# 6way.net
KiCad netlist of a schematic drawn in EAGLE
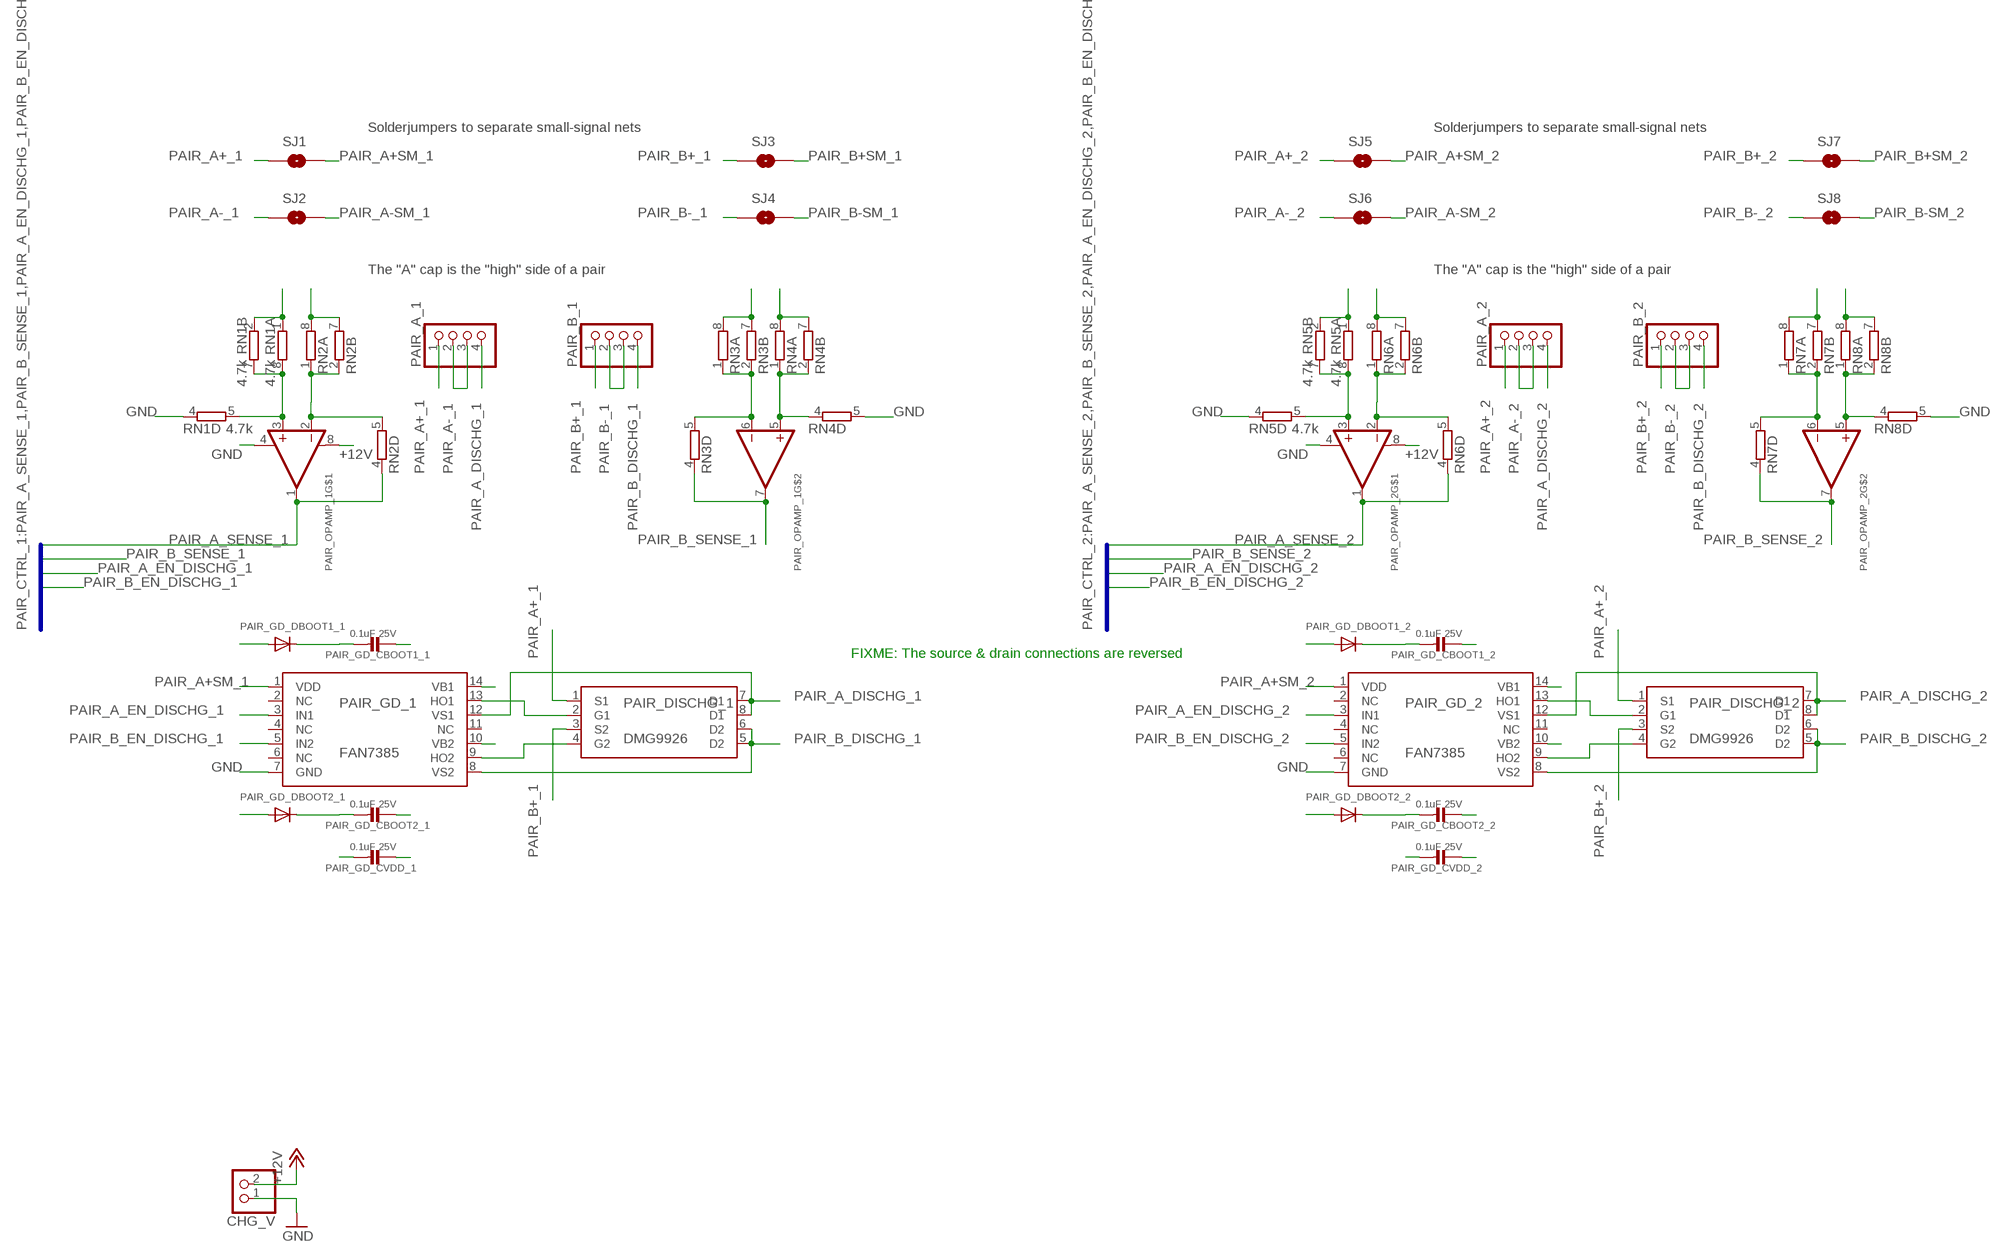
[diagram p0: schematic, sheet 1, part 1 of 2]
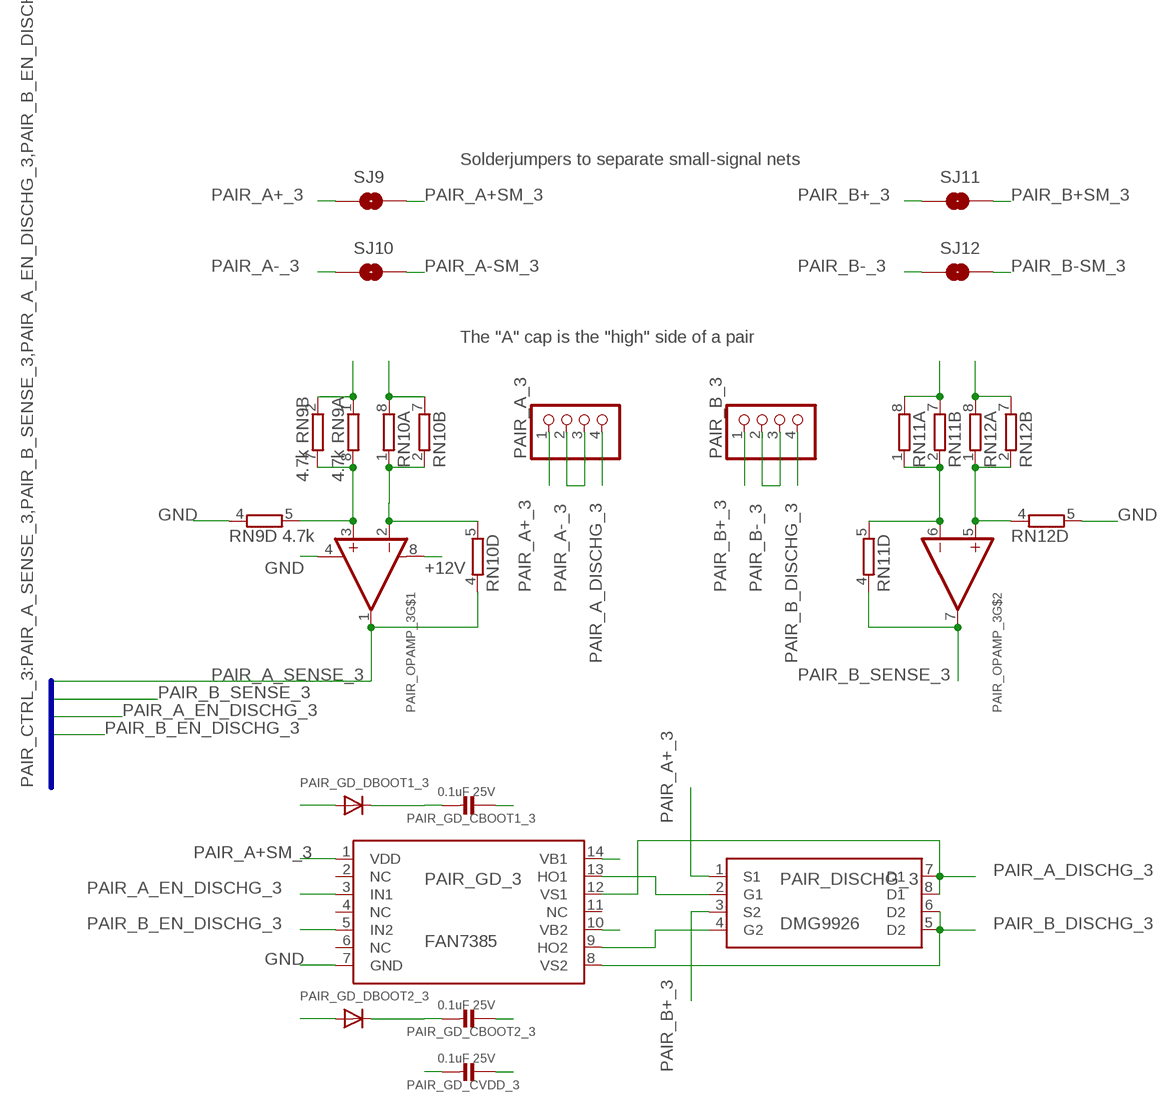
[diagram p1: schematic, sheet 1, part 2 of 2]

(export (version "E")
  (design (tool "Eeschema 10.0.6"))
  (components
    (comp (ref "CHG_V")
      (value "PINHD-1X2")
      (footprint "eagle-import:1X02")
      (libsource (lib "eagle-import") (part "PINHD-1X2"))
    )
    (comp (ref "PAIR_A_1")
      (value "PINHD-1X4")
      (footprint "eagle-import:1X04")
      (libsource (lib "eagle-import") (part "PINHD-1X4"))
    )
    (comp (ref "PAIR_A_2")
      (value "PINHD-1X4")
      (footprint "eagle-import:1X04")
      (libsource (lib "eagle-import") (part "PINHD-1X4"))
    )
    (comp (ref "PAIR_A_3")
      (value "PINHD-1X4")
      (footprint "eagle-import:1X04")
      (libsource (lib "eagle-import") (part "PINHD-1X4"))
    )
    (comp (ref "PAIR_B_1")
      (value "PINHD-1X4")
      (footprint "eagle-import:1X04")
      (libsource (lib "eagle-import") (part "PINHD-1X4"))
    )
    (comp (ref "PAIR_B_2")
      (value "PINHD-1X4")
      (footprint "eagle-import:1X04")
      (libsource (lib "eagle-import") (part "PINHD-1X4"))
    )
    (comp (ref "PAIR_B_3")
      (value "PINHD-1X4")
      (footprint "eagle-import:1X04")
      (libsource (lib "eagle-import") (part "PINHD-1X4"))
    )
    (comp (ref "PAIR_DISCHG_1")
      (value "DMG9926")
      (footprint "eagle-import:SOP8-L")
      (libsource (lib "eagle-import") (part "DMG9926"))
    )
    (comp (ref "PAIR_DISCHG_2")
      (value "DMG9926")
      (footprint "eagle-import:SOP8-L")
      (libsource (lib "eagle-import") (part "DMG9926"))
    )
    (comp (ref "PAIR_DISCHG_3")
      (value "DMG9926")
      (footprint "eagle-import:SOP8-L")
      (libsource (lib "eagle-import") (part "DMG9926"))
    )
    (comp (ref "PAIR_GD_1")
      (value "FAN7385")
      (footprint "eagle-import:SOT14")
      (libsource (lib "eagle-import") (part "FAN7385"))
    )
    (comp (ref "PAIR_GD_2")
      (value "FAN7385")
      (footprint "eagle-import:SOT14")
      (libsource (lib "eagle-import") (part "FAN7385"))
    )
    (comp (ref "PAIR_GD_3")
      (value "FAN7385")
      (footprint "eagle-import:SOT14")
      (libsource (lib "eagle-import") (part "FAN7385"))
    )
    (comp (ref "PAIR_GD_CBOOT1_1")
      (value "0.1uF 25V")
      (footprint "eagle-import:0805")
      (libsource (lib "eagle-import") (part "CAP_CERAMIC0805"))
    )
    (comp (ref "PAIR_GD_CBOOT1_2")
      (value "0.1uF 25V")
      (footprint "eagle-import:0805")
      (libsource (lib "eagle-import") (part "CAP_CERAMIC0805"))
    )
    (comp (ref "PAIR_GD_CBOOT1_3")
      (value "0.1uF 25V")
      (footprint "eagle-import:0805")
      (libsource (lib "eagle-import") (part "CAP_CERAMIC0805"))
    )
    (comp (ref "PAIR_GD_CBOOT2_1")
      (value "0.1uF 25V")
      (footprint "eagle-import:0805")
      (libsource (lib "eagle-import") (part "CAP_CERAMIC0805"))
    )
    (comp (ref "PAIR_GD_CBOOT2_2")
      (value "0.1uF 25V")
      (footprint "eagle-import:0805")
      (libsource (lib "eagle-import") (part "CAP_CERAMIC0805"))
    )
    (comp (ref "PAIR_GD_CBOOT2_3")
      (value "0.1uF 25V")
      (footprint "eagle-import:0805")
      (libsource (lib "eagle-import") (part "CAP_CERAMIC0805"))
    )
    (comp (ref "PAIR_GD_CVDD_1")
      (value "0.1uF 25V")
      (footprint "eagle-import:0805")
      (libsource (lib "eagle-import") (part "CAP_CERAMIC0805"))
    )
    (comp (ref "PAIR_GD_CVDD_2")
      (value "0.1uF 25V")
      (footprint "eagle-import:0805")
      (libsource (lib "eagle-import") (part "CAP_CERAMIC0805"))
    )
    (comp (ref "PAIR_GD_CVDD_3")
      (value "0.1uF 25V")
      (footprint "eagle-import:0805")
      (libsource (lib "eagle-import") (part "CAP_CERAMIC0805"))
    )
    (comp (ref "PAIR_GD_DBOOT1_1")
      (value "DIODESOT23_WIDE")
      (footprint "eagle-import:SOT23-WIDE")
      (libsource (lib "eagle-import") (part "DIODESOT23_WIDE"))
    )
    (comp (ref "PAIR_GD_DBOOT1_2")
      (value "DIODESOT23_WIDE")
      (footprint "eagle-import:SOT23-WIDE")
      (libsource (lib "eagle-import") (part "DIODESOT23_WIDE"))
    )
    (comp (ref "PAIR_GD_DBOOT1_3")
      (value "DIODESOT23_WIDE")
      (footprint "eagle-import:SOT23-WIDE")
      (libsource (lib "eagle-import") (part "DIODESOT23_WIDE"))
    )
    (comp (ref "PAIR_GD_DBOOT2_1")
      (value "DIODESOT23_WIDE")
      (footprint "eagle-import:SOT23-WIDE")
      (libsource (lib "eagle-import") (part "DIODESOT23_WIDE"))
    )
    (comp (ref "PAIR_GD_DBOOT2_2")
      (value "DIODESOT23_WIDE")
      (footprint "eagle-import:SOT23-WIDE")
      (libsource (lib "eagle-import") (part "DIODESOT23_WIDE"))
    )
    (comp (ref "PAIR_GD_DBOOT2_3")
      (value "DIODESOT23_WIDE")
      (footprint "eagle-import:SOT23-WIDE")
      (libsource (lib "eagle-import") (part "DIODESOT23_WIDE"))
    )
    (comp (ref "PAIR_OPAMP_1")
      (value "LM358")
      (footprint "eagle-import:SOIC8_150MIL")
      (libsource (lib "eagle-import") (part "LM358"))
    )
    (comp (ref "PAIR_OPAMP_2")
      (value "LM358")
      (footprint "eagle-import:SOIC8_150MIL")
      (libsource (lib "eagle-import") (part "LM358"))
    )
    (comp (ref "PAIR_OPAMP_3")
      (value "LM358")
      (footprint "eagle-import:SOIC8_150MIL")
      (libsource (lib "eagle-import") (part "LM358"))
    )
    (comp (ref "RN1")
      (value "4.7k")
      (footprint "eagle-import:CAY16")
      (libsource (lib "eagle-import") (part "4R-NCAY16"))
    )
    (comp (ref "RN2")
      (value "4R-NCAY16")
      (footprint "eagle-import:CAY16")
      (libsource (lib "eagle-import") (part "4R-NCAY16"))
    )
    (comp (ref "RN3")
      (value "4R-NCAY16")
      (footprint "eagle-import:CAY16")
      (libsource (lib "eagle-import") (part "4R-NCAY16"))
    )
    (comp (ref "RN4")
      (value "4R-NCAY16")
      (footprint "eagle-import:CAY16")
      (libsource (lib "eagle-import") (part "4R-NCAY16"))
    )
    (comp (ref "RN5")
      (value "4.7k")
      (footprint "eagle-import:CAY16")
      (libsource (lib "eagle-import") (part "4R-NCAY16"))
    )
    (comp (ref "RN6")
      (value "4R-NCAY16")
      (footprint "eagle-import:CAY16")
      (libsource (lib "eagle-import") (part "4R-NCAY16"))
    )
    (comp (ref "RN7")
      (value "4R-NCAY16")
      (footprint "eagle-import:CAY16")
      (libsource (lib "eagle-import") (part "4R-NCAY16"))
    )
    (comp (ref "RN8")
      (value "4R-NCAY16")
      (footprint "eagle-import:CAY16")
      (libsource (lib "eagle-import") (part "4R-NCAY16"))
    )
    (comp (ref "RN9")
      (value "4.7k")
      (footprint "eagle-import:CAY16")
      (libsource (lib "eagle-import") (part "4R-NCAY16"))
    )
    (comp (ref "RN10")
      (value "4R-NCAY16")
      (footprint "eagle-import:CAY16")
      (libsource (lib "eagle-import") (part "4R-NCAY16"))
    )
    (comp (ref "RN11")
      (value "4R-NCAY16")
      (footprint "eagle-import:CAY16")
      (libsource (lib "eagle-import") (part "4R-NCAY16"))
    )
    (comp (ref "RN12")
      (value "4R-NCAY16")
      (footprint "eagle-import:CAY16")
      (libsource (lib "eagle-import") (part "4R-NCAY16"))
    )
    (comp (ref "SJ1")
      (value "SOLDERJUMPERTRACE")
      (footprint "eagle-import:SJ_2S-TRACE")
      (libsource (lib "eagle-import") (part "SOLDERJUMPERTRACE"))
    )
    (comp (ref "SJ2")
      (value "SOLDERJUMPERTRACE")
      (footprint "eagle-import:SJ_2S-TRACE")
      (libsource (lib "eagle-import") (part "SOLDERJUMPERTRACE"))
    )
    (comp (ref "SJ3")
      (value "SOLDERJUMPERTRACE")
      (footprint "eagle-import:SJ_2S-TRACE")
      (libsource (lib "eagle-import") (part "SOLDERJUMPERTRACE"))
    )
    (comp (ref "SJ4")
      (value "SOLDERJUMPERTRACE")
      (footprint "eagle-import:SJ_2S-TRACE")
      (libsource (lib "eagle-import") (part "SOLDERJUMPERTRACE"))
    )
    (comp (ref "SJ5")
      (value "SOLDERJUMPERTRACE")
      (footprint "eagle-import:SJ_2S-TRACE")
      (libsource (lib "eagle-import") (part "SOLDERJUMPERTRACE"))
    )
    (comp (ref "SJ6")
      (value "SOLDERJUMPERTRACE")
      (footprint "eagle-import:SJ_2S-TRACE")
      (libsource (lib "eagle-import") (part "SOLDERJUMPERTRACE"))
    )
    (comp (ref "SJ7")
      (value "SOLDERJUMPERTRACE")
      (footprint "eagle-import:SJ_2S-TRACE")
      (libsource (lib "eagle-import") (part "SOLDERJUMPERTRACE"))
    )
    (comp (ref "SJ8")
      (value "SOLDERJUMPERTRACE")
      (footprint "eagle-import:SJ_2S-TRACE")
      (libsource (lib "eagle-import") (part "SOLDERJUMPERTRACE"))
    )
    (comp (ref "SJ9")
      (value "SOLDERJUMPERTRACE")
      (footprint "eagle-import:SJ_2S-TRACE")
      (libsource (lib "eagle-import") (part "SOLDERJUMPERTRACE"))
    )
    (comp (ref "SJ10")
      (value "SOLDERJUMPERTRACE")
      (footprint "eagle-import:SJ_2S-TRACE")
      (libsource (lib "eagle-import") (part "SOLDERJUMPERTRACE"))
    )
    (comp (ref "SJ11")
      (value "SOLDERJUMPERTRACE")
      (footprint "eagle-import:SJ_2S-TRACE")
      (libsource (lib "eagle-import") (part "SOLDERJUMPERTRACE"))
    )
    (comp (ref "SJ12")
      (value "SOLDERJUMPERTRACE")
      (footprint "eagle-import:SJ_2S-TRACE")
      (libsource (lib "eagle-import") (part "SOLDERJUMPERTRACE"))
    )
  )
  (nets
    (net (code "4") (name "+12V") (class "Default")
      (node (ref "CHG_V") (pin "2") (pinfunction "2_2") (pintype "passive"))
      (node (ref "PAIR_OPAMP_1") (pin "8") (pinfunction "V+_8") (pintype "power_in"))
      (node (ref "PAIR_OPAMP_2") (pin "8") (pinfunction "V+_8") (pintype "power_in"))
      (node (ref "PAIR_OPAMP_3") (pin "8") (pinfunction "V+_8") (pintype "power_in"))
    )
    (net (code "5") (name "/PAIR_A+SM_1") (class "Default")
      (node (ref "PAIR_GD_1") (pin "1") (pinfunction "VDD_1") (pintype "power_in"))
      (node (ref "PAIR_GD_CVDD_1") (pin "2") (pinfunction "P$2_2") (pintype "passive"))
      (node (ref "PAIR_GD_DBOOT1_1") (pin "1") (pinfunction "A_1") (pintype "passive"))
      (node (ref "PAIR_GD_DBOOT2_1") (pin "1") (pinfunction "A_1") (pintype "passive"))
      (node (ref "RN1") (pin "1") (pinfunction "1_1") (pintype "passive"))
      (node (ref "RN1") (pin "2") (pinfunction "1_2") (pintype "passive"))
      (node (ref "SJ1") (pin "2") (pinfunction "2_2") (pintype "passive"))
    )
    (net (code "6") (name "/PAIR_A+SM_2") (class "Default")
      (node (ref "PAIR_GD_2") (pin "1") (pinfunction "VDD_1") (pintype "power_in"))
      (node (ref "PAIR_GD_CVDD_2") (pin "2") (pinfunction "P$2_2") (pintype "passive"))
      (node (ref "PAIR_GD_DBOOT1_2") (pin "1") (pinfunction "A_1") (pintype "passive"))
      (node (ref "PAIR_GD_DBOOT2_2") (pin "1") (pinfunction "A_1") (pintype "passive"))
      (node (ref "RN5") (pin "1") (pinfunction "1_1") (pintype "passive"))
      (node (ref "RN5") (pin "2") (pinfunction "1_2") (pintype "passive"))
      (node (ref "SJ5") (pin "2") (pinfunction "2_2") (pintype "passive"))
    )
    (net (code "7") (name "/PAIR_A+SM_3") (class "Default")
      (node (ref "PAIR_GD_3") (pin "1") (pinfunction "VDD_1") (pintype "power_in"))
      (node (ref "PAIR_GD_CVDD_3") (pin "2") (pinfunction "P$2_2") (pintype "passive"))
      (node (ref "PAIR_GD_DBOOT1_3") (pin "1") (pinfunction "A_1") (pintype "passive"))
      (node (ref "PAIR_GD_DBOOT2_3") (pin "1") (pinfunction "A_1") (pintype "passive"))
      (node (ref "RN9") (pin "1") (pinfunction "1_1") (pintype "passive"))
      (node (ref "RN9") (pin "2") (pinfunction "1_2") (pintype "passive"))
      (node (ref "SJ9") (pin "2") (pinfunction "2_2") (pintype "passive"))
    )
    (net (code "8") (name "/PAIR_A+_1") (class "Default")
      (node (ref "PAIR_A_1") (pin "1") (pinfunction "1_1") (pintype "passive"))
      (node (ref "PAIR_DISCHG_1") (pin "1") (pinfunction "S1_1") (pintype "input"))
      (node (ref "SJ1") (pin "1") (pinfunction "1_1") (pintype "passive"))
    )
    (net (code "9") (name "/PAIR_A+_2") (class "Default")
      (node (ref "PAIR_A_2") (pin "1") (pinfunction "1_1") (pintype "passive"))
      (node (ref "PAIR_DISCHG_2") (pin "1") (pinfunction "S1_1") (pintype "input"))
      (node (ref "SJ5") (pin "1") (pinfunction "1_1") (pintype "passive"))
    )
    (net (code "10") (name "/PAIR_A+_3") (class "Default")
      (node (ref "PAIR_A_3") (pin "1") (pinfunction "1_1") (pintype "passive"))
      (node (ref "PAIR_DISCHG_3") (pin "1") (pinfunction "S1_1") (pintype "input"))
      (node (ref "SJ9") (pin "1") (pinfunction "1_1") (pintype "passive"))
    )
    (net (code "11") (name "/PAIR_A-SM_1") (class "Default")
      (node (ref "RN2") (pin "7") (pinfunction "2_7") (pintype "passive"))
      (node (ref "RN2") (pin "8") (pinfunction "2_8") (pintype "passive"))
      (node (ref "SJ2") (pin "2") (pinfunction "2_2") (pintype "passive"))
    )
    (net (code "12") (name "/PAIR_A-SM_2") (class "Default")
      (node (ref "RN6") (pin "7") (pinfunction "2_7") (pintype "passive"))
      (node (ref "RN6") (pin "8") (pinfunction "2_8") (pintype "passive"))
      (node (ref "SJ6") (pin "2") (pinfunction "2_2") (pintype "passive"))
    )
    (net (code "13") (name "/PAIR_A-SM_3") (class "Default")
      (node (ref "RN10") (pin "7") (pinfunction "2_7") (pintype "passive"))
      (node (ref "RN10") (pin "8") (pinfunction "2_8") (pintype "passive"))
      (node (ref "SJ10") (pin "2") (pinfunction "2_2") (pintype "passive"))
    )
    (net (code "14") (name "/PAIR_A-_1") (class "Default")
      (node (ref "PAIR_A_1") (pin "2") (pinfunction "2_2") (pintype "passive"))
      (node (ref "PAIR_A_1") (pin "3") (pinfunction "3_3") (pintype "passive"))
      (node (ref "SJ2") (pin "1") (pinfunction "1_1") (pintype "passive"))
    )
    (net (code "15") (name "/PAIR_A-_2") (class "Default")
      (node (ref "PAIR_A_2") (pin "2") (pinfunction "2_2") (pintype "passive"))
      (node (ref "PAIR_A_2") (pin "3") (pinfunction "3_3") (pintype "passive"))
      (node (ref "SJ6") (pin "1") (pinfunction "1_1") (pintype "passive"))
    )
    (net (code "16") (name "/PAIR_A-_3") (class "Default")
      (node (ref "PAIR_A_3") (pin "2") (pinfunction "2_2") (pintype "passive"))
      (node (ref "PAIR_A_3") (pin "3") (pinfunction "3_3") (pintype "passive"))
      (node (ref "SJ10") (pin "1") (pinfunction "1_1") (pintype "passive"))
    )
    (net (code "17") (name "/PAIR_A_DISCHG_1") (class "Default")
      (node (ref "PAIR_A_1") (pin "4") (pinfunction "4_4") (pintype "passive"))
      (node (ref "PAIR_DISCHG_1") (pin "7") (pinfunction "D1_7") (pintype "output"))
      (node (ref "PAIR_DISCHG_1") (pin "8") (pinfunction "D1_8") (pintype "output"))
      (node (ref "PAIR_GD_1") (pin "12") (pinfunction "VS1_12") (pintype "input"))
      (node (ref "PAIR_GD_CBOOT1_1") (pin "1") (pinfunction "P$1_1") (pintype "passive"))
    )
    (net (code "18") (name "/PAIR_A_DISCHG_2") (class "Default")
      (node (ref "PAIR_A_2") (pin "4") (pinfunction "4_4") (pintype "passive"))
      (node (ref "PAIR_DISCHG_2") (pin "7") (pinfunction "D1_7") (pintype "output"))
      (node (ref "PAIR_DISCHG_2") (pin "8") (pinfunction "D1_8") (pintype "output"))
      (node (ref "PAIR_GD_2") (pin "12") (pinfunction "VS1_12") (pintype "input"))
      (node (ref "PAIR_GD_CBOOT1_2") (pin "1") (pinfunction "P$1_1") (pintype "passive"))
    )
    (net (code "19") (name "/PAIR_A_DISCHG_3") (class "Default")
      (node (ref "PAIR_A_3") (pin "4") (pinfunction "4_4") (pintype "passive"))
      (node (ref "PAIR_DISCHG_3") (pin "7") (pinfunction "D1_7") (pintype "output"))
      (node (ref "PAIR_DISCHG_3") (pin "8") (pinfunction "D1_8") (pintype "output"))
      (node (ref "PAIR_GD_3") (pin "12") (pinfunction "VS1_12") (pintype "input"))
      (node (ref "PAIR_GD_CBOOT1_3") (pin "1") (pinfunction "P$1_1") (pintype "passive"))
    )
    (net (code "20") (name "/PAIR_A_EN_DISCHG_1") (class "Default")
      (node (ref "PAIR_GD_1") (pin "3") (pinfunction "IN1_3") (pintype "input"))
    )
    (net (code "21") (name "/PAIR_A_EN_DISCHG_2") (class "Default")
      (node (ref "PAIR_GD_2") (pin "3") (pinfunction "IN1_3") (pintype "input"))
    )
    (net (code "22") (name "/PAIR_A_EN_DISCHG_3") (class "Default")
      (node (ref "PAIR_GD_3") (pin "3") (pinfunction "IN1_3") (pintype "input"))
    )
    (net (code "23") (name "/PAIR_A_SENSE_1") (class "Default")
      (node (ref "PAIR_OPAMP_1") (pin "1") (pinfunction "OUT_1") (pintype "output"))
      (node (ref "RN2") (pin "4") (pinfunction "1_4") (pintype "passive"))
    )
    (net (code "24") (name "/PAIR_A_SENSE_2") (class "Default")
      (node (ref "PAIR_OPAMP_2") (pin "1") (pinfunction "OUT_1") (pintype "output"))
      (node (ref "RN6") (pin "4") (pinfunction "1_4") (pintype "passive"))
    )
    (net (code "25") (name "/PAIR_A_SENSE_3") (class "Default")
      (node (ref "PAIR_OPAMP_3") (pin "1") (pinfunction "OUT_1") (pintype "output"))
      (node (ref "RN10") (pin "4") (pinfunction "1_4") (pintype "passive"))
    )
    (net (code "26") (name "/PAIR_B+SM_1") (class "Default")
      (node (ref "RN4") (pin "7") (pinfunction "2_7") (pintype "passive"))
      (node (ref "RN4") (pin "8") (pinfunction "2_8") (pintype "passive"))
      (node (ref "SJ3") (pin "2") (pinfunction "2_2") (pintype "passive"))
    )
    (net (code "27") (name "/PAIR_B+SM_2") (class "Default")
      (node (ref "RN8") (pin "7") (pinfunction "2_7") (pintype "passive"))
      (node (ref "RN8") (pin "8") (pinfunction "2_8") (pintype "passive"))
      (node (ref "SJ7") (pin "2") (pinfunction "2_2") (pintype "passive"))
    )
    (net (code "28") (name "/PAIR_B+SM_3") (class "Default")
      (node (ref "RN12") (pin "7") (pinfunction "2_7") (pintype "passive"))
      (node (ref "RN12") (pin "8") (pinfunction "2_8") (pintype "passive"))
      (node (ref "SJ11") (pin "2") (pinfunction "2_2") (pintype "passive"))
    )
    (net (code "29") (name "/PAIR_B+_1") (class "Default")
      (node (ref "PAIR_B_1") (pin "1") (pinfunction "1_1") (pintype "passive"))
      (node (ref "PAIR_DISCHG_1") (pin "3") (pinfunction "S2_3") (pintype "input"))
      (node (ref "SJ3") (pin "1") (pinfunction "1_1") (pintype "passive"))
    )
    (net (code "30") (name "/PAIR_B+_2") (class "Default")
      (node (ref "PAIR_B_2") (pin "1") (pinfunction "1_1") (pintype "passive"))
      (node (ref "PAIR_DISCHG_2") (pin "3") (pinfunction "S2_3") (pintype "input"))
      (node (ref "SJ7") (pin "1") (pinfunction "1_1") (pintype "passive"))
    )
    (net (code "31") (name "/PAIR_B+_3") (class "Default")
      (node (ref "PAIR_B_3") (pin "1") (pinfunction "1_1") (pintype "passive"))
      (node (ref "PAIR_DISCHG_3") (pin "3") (pinfunction "S2_3") (pintype "input"))
      (node (ref "SJ11") (pin "1") (pinfunction "1_1") (pintype "passive"))
    )
    (net (code "32") (name "/PAIR_B-SM_1") (class "Default")
      (node (ref "RN3") (pin "7") (pinfunction "2_7") (pintype "passive"))
      (node (ref "RN3") (pin "8") (pinfunction "2_8") (pintype "passive"))
      (node (ref "SJ4") (pin "2") (pinfunction "2_2") (pintype "passive"))
    )
    (net (code "33") (name "/PAIR_B-SM_2") (class "Default")
      (node (ref "RN7") (pin "7") (pinfunction "2_7") (pintype "passive"))
      (node (ref "RN7") (pin "8") (pinfunction "2_8") (pintype "passive"))
      (node (ref "SJ8") (pin "2") (pinfunction "2_2") (pintype "passive"))
    )
    (net (code "34") (name "/PAIR_B-SM_3") (class "Default")
      (node (ref "RN11") (pin "7") (pinfunction "2_7") (pintype "passive"))
      (node (ref "RN11") (pin "8") (pinfunction "2_8") (pintype "passive"))
      (node (ref "SJ12") (pin "2") (pinfunction "2_2") (pintype "passive"))
    )
    (net (code "35") (name "/PAIR_B-_1") (class "Default")
      (node (ref "PAIR_B_1") (pin "2") (pinfunction "2_2") (pintype "passive"))
      (node (ref "PAIR_B_1") (pin "3") (pinfunction "3_3") (pintype "passive"))
      (node (ref "SJ4") (pin "1") (pinfunction "1_1") (pintype "passive"))
    )
    (net (code "36") (name "/PAIR_B-_2") (class "Default")
      (node (ref "PAIR_B_2") (pin "2") (pinfunction "2_2") (pintype "passive"))
      (node (ref "PAIR_B_2") (pin "3") (pinfunction "3_3") (pintype "passive"))
      (node (ref "SJ8") (pin "1") (pinfunction "1_1") (pintype "passive"))
    )
    (net (code "37") (name "/PAIR_B-_3") (class "Default")
      (node (ref "PAIR_B_3") (pin "2") (pinfunction "2_2") (pintype "passive"))
      (node (ref "PAIR_B_3") (pin "3") (pinfunction "3_3") (pintype "passive"))
      (node (ref "SJ12") (pin "1") (pinfunction "1_1") (pintype "passive"))
    )
    (net (code "38") (name "/PAIR_B_DISCHG_1") (class "Default")
      (node (ref "PAIR_B_1") (pin "4") (pinfunction "4_4") (pintype "passive"))
      (node (ref "PAIR_DISCHG_1") (pin "5") (pinfunction "D2_5") (pintype "output"))
      (node (ref "PAIR_DISCHG_1") (pin "6") (pinfunction "D2_6") (pintype "output"))
      (node (ref "PAIR_GD_1") (pin "8") (pinfunction "VS2_8") (pintype "input"))
      (node (ref "PAIR_GD_CBOOT2_1") (pin "1") (pinfunction "P$1_1") (pintype "passive"))
    )
    (net (code "39") (name "/PAIR_B_DISCHG_2") (class "Default")
      (node (ref "PAIR_B_2") (pin "4") (pinfunction "4_4") (pintype "passive"))
      (node (ref "PAIR_DISCHG_2") (pin "5") (pinfunction "D2_5") (pintype "output"))
      (node (ref "PAIR_DISCHG_2") (pin "6") (pinfunction "D2_6") (pintype "output"))
      (node (ref "PAIR_GD_2") (pin "8") (pinfunction "VS2_8") (pintype "input"))
      (node (ref "PAIR_GD_CBOOT2_2") (pin "1") (pinfunction "P$1_1") (pintype "passive"))
    )
    (net (code "40") (name "/PAIR_B_DISCHG_3") (class "Default")
      (node (ref "PAIR_B_3") (pin "4") (pinfunction "4_4") (pintype "passive"))
      (node (ref "PAIR_DISCHG_3") (pin "5") (pinfunction "D2_5") (pintype "output"))
      (node (ref "PAIR_DISCHG_3") (pin "6") (pinfunction "D2_6") (pintype "output"))
      (node (ref "PAIR_GD_3") (pin "8") (pinfunction "VS2_8") (pintype "input"))
      (node (ref "PAIR_GD_CBOOT2_3") (pin "1") (pinfunction "P$1_1") (pintype "passive"))
    )
    (net (code "41") (name "/PAIR_B_EN_DISCHG_1") (class "Default")
      (node (ref "PAIR_GD_1") (pin "5") (pinfunction "IN2_5") (pintype "input"))
    )
    (net (code "42") (name "/PAIR_B_EN_DISCHG_2") (class "Default")
      (node (ref "PAIR_GD_2") (pin "5") (pinfunction "IN2_5") (pintype "input"))
    )
    (net (code "43") (name "/PAIR_B_EN_DISCHG_3") (class "Default")
      (node (ref "PAIR_GD_3") (pin "5") (pinfunction "IN2_5") (pintype "input"))
    )
    (net (code "44") (name "/PAIR_B_SENSE_1") (class "Default")
      (node (ref "PAIR_OPAMP_1") (pin "7") (pinfunction "OUT_7") (pintype "output"))
      (node (ref "RN3") (pin "4") (pinfunction "1_4") (pintype "passive"))
    )
    (net (code "45") (name "/PAIR_B_SENSE_2") (class "Default")
      (node (ref "PAIR_OPAMP_2") (pin "7") (pinfunction "OUT_7") (pintype "output"))
      (node (ref "RN7") (pin "4") (pinfunction "1_4") (pintype "passive"))
    )
    (net (code "46") (name "/PAIR_B_SENSE_3") (class "Default")
      (node (ref "PAIR_OPAMP_3") (pin "7") (pinfunction "OUT_7") (pintype "output"))
      (node (ref "RN11") (pin "4") (pinfunction "1_4") (pintype "passive"))
    )
    (net (code "47") (name "/PAIR_GD_VB1_1") (class "Default")
      (node (ref "PAIR_GD_1") (pin "14") (pinfunction "VB1_14") (pintype "input"))
      (node (ref "PAIR_GD_CBOOT1_1") (pin "2") (pinfunction "P$2_2") (pintype "passive"))
      (node (ref "PAIR_GD_DBOOT1_1") (pin "3") (pinfunction "C_3") (pintype "passive"))
    )
    (net (code "48") (name "/PAIR_GD_VB1_2") (class "Default")
      (node (ref "PAIR_GD_2") (pin "14") (pinfunction "VB1_14") (pintype "input"))
      (node (ref "PAIR_GD_CBOOT1_2") (pin "2") (pinfunction "P$2_2") (pintype "passive"))
      (node (ref "PAIR_GD_DBOOT1_2") (pin "3") (pinfunction "C_3") (pintype "passive"))
    )
    (net (code "49") (name "/PAIR_GD_VB1_3") (class "Default")
      (node (ref "PAIR_GD_3") (pin "14") (pinfunction "VB1_14") (pintype "input"))
      (node (ref "PAIR_GD_CBOOT1_3") (pin "2") (pinfunction "P$2_2") (pintype "passive"))
      (node (ref "PAIR_GD_DBOOT1_3") (pin "3") (pinfunction "C_3") (pintype "passive"))
    )
    (net (code "50") (name "/PAIR_GD_VB2_1") (class "Default")
      (node (ref "PAIR_GD_1") (pin "10") (pinfunction "VB2_10") (pintype "input"))
      (node (ref "PAIR_GD_CBOOT2_1") (pin "2") (pinfunction "P$2_2") (pintype "passive"))
      (node (ref "PAIR_GD_DBOOT2_1") (pin "3") (pinfunction "C_3") (pintype "passive"))
    )
    (net (code "51") (name "/PAIR_GD_VB2_2") (class "Default")
      (node (ref "PAIR_GD_2") (pin "10") (pinfunction "VB2_10") (pintype "input"))
      (node (ref "PAIR_GD_CBOOT2_2") (pin "2") (pinfunction "P$2_2") (pintype "passive"))
      (node (ref "PAIR_GD_DBOOT2_2") (pin "3") (pinfunction "C_3") (pintype "passive"))
    )
    (net (code "52") (name "/PAIR_GD_VB2_3") (class "Default")
      (node (ref "PAIR_GD_3") (pin "10") (pinfunction "VB2_10") (pintype "input"))
      (node (ref "PAIR_GD_CBOOT2_3") (pin "2") (pinfunction "P$2_2") (pintype "passive"))
      (node (ref "PAIR_GD_DBOOT2_3") (pin "3") (pinfunction "C_3") (pintype "passive"))
    )
    (net (code "56") (name "GND") (class "Default")
      (node (ref "CHG_V") (pin "1") (pinfunction "1_1") (pintype "passive"))
      (node (ref "PAIR_GD_1") (pin "7") (pinfunction "GND_7") (pintype "power_in"))
      (node (ref "PAIR_GD_2") (pin "7") (pinfunction "GND_7") (pintype "power_in"))
      (node (ref "PAIR_GD_3") (pin "7") (pinfunction "GND_7") (pintype "power_in"))
      (node (ref "PAIR_GD_CVDD_1") (pin "1") (pinfunction "P$1_1") (pintype "passive"))
      (node (ref "PAIR_GD_CVDD_2") (pin "1") (pinfunction "P$1_1") (pintype "passive"))
      (node (ref "PAIR_GD_CVDD_3") (pin "1") (pinfunction "P$1_1") (pintype "passive"))
      (node (ref "PAIR_OPAMP_1") (pin "4") (pinfunction "V-_4") (pintype "power_in"))
      (node (ref "PAIR_OPAMP_2") (pin "4") (pinfunction "V-_4") (pintype "power_in"))
      (node (ref "PAIR_OPAMP_3") (pin "4") (pinfunction "V-_4") (pintype "power_in"))
      (node (ref "RN1") (pin "4") (pinfunction "1_4") (pintype "passive"))
      (node (ref "RN12") (pin "5") (pinfunction "2_5") (pintype "passive"))
      (node (ref "RN4") (pin "5") (pinfunction "2_5") (pintype "passive"))
      (node (ref "RN5") (pin "4") (pinfunction "1_4") (pintype "passive"))
      (node (ref "RN8") (pin "5") (pinfunction "2_5") (pintype "passive"))
      (node (ref "RN9") (pin "4") (pinfunction "1_4") (pintype "passive"))
    )
    (net (code "57") (name "Net-(PAIR_DISCHG_1-G1)") (class "Default")
      (node (ref "PAIR_DISCHG_1") (pin "2") (pinfunction "G1_2") (pintype "input"))
      (node (ref "PAIR_GD_1") (pin "13") (pinfunction "HO1_13") (pintype "output"))
    )
    (net (code "58") (name "Net-(PAIR_DISCHG_1-G2)") (class "Default")
      (node (ref "PAIR_DISCHG_1") (pin "4") (pinfunction "G2_4") (pintype "input"))
      (node (ref "PAIR_GD_1") (pin "9") (pinfunction "HO2_9") (pintype "output"))
    )
    (net (code "59") (name "Net-(PAIR_DISCHG_2-G1)") (class "Default")
      (node (ref "PAIR_DISCHG_2") (pin "2") (pinfunction "G1_2") (pintype "input"))
      (node (ref "PAIR_GD_2") (pin "13") (pinfunction "HO1_13") (pintype "output"))
    )
    (net (code "60") (name "Net-(PAIR_DISCHG_2-G2)") (class "Default")
      (node (ref "PAIR_DISCHG_2") (pin "4") (pinfunction "G2_4") (pintype "input"))
      (node (ref "PAIR_GD_2") (pin "9") (pinfunction "HO2_9") (pintype "output"))
    )
    (net (code "61") (name "Net-(PAIR_DISCHG_3-G1)") (class "Default")
      (node (ref "PAIR_DISCHG_3") (pin "2") (pinfunction "G1_2") (pintype "input"))
      (node (ref "PAIR_GD_3") (pin "13") (pinfunction "HO1_13") (pintype "output"))
    )
    (net (code "62") (name "Net-(PAIR_DISCHG_3-G2)") (class "Default")
      (node (ref "PAIR_DISCHG_3") (pin "4") (pinfunction "G2_4") (pintype "input"))
      (node (ref "PAIR_GD_3") (pin "9") (pinfunction "HO2_9") (pintype "output"))
    )
    (net (code "63") (name "Net-(PAIR_OPAMP_1A-+IN)") (class "Default")
      (node (ref "PAIR_OPAMP_1") (pin "3") (pinfunction "+IN_3") (pintype "input"))
      (node (ref "RN1") (pin "5") (pinfunction "2_5") (pintype "passive"))
      (node (ref "RN1") (pin "7") (pinfunction "2_7") (pintype "passive"))
      (node (ref "RN1") (pin "8") (pinfunction "2_8") (pintype "passive"))
    )
    (net (code "64") (name "Net-(PAIR_OPAMP_1A--IN)") (class "Default")
      (node (ref "PAIR_OPAMP_1") (pin "2") (pinfunction "-IN_2") (pintype "input"))
      (node (ref "RN2") (pin "1") (pinfunction "1_1") (pintype "passive"))
      (node (ref "RN2") (pin "2") (pinfunction "1_2") (pintype "passive"))
      (node (ref "RN2") (pin "5") (pinfunction "2_5") (pintype "passive"))
    )
    (net (code "65") (name "Net-(PAIR_OPAMP_1B-+IN)") (class "Default")
      (node (ref "PAIR_OPAMP_1") (pin "5") (pinfunction "+IN_5") (pintype "input"))
      (node (ref "RN4") (pin "1") (pinfunction "1_1") (pintype "passive"))
      (node (ref "RN4") (pin "2") (pinfunction "1_2") (pintype "passive"))
      (node (ref "RN4") (pin "4") (pinfunction "1_4") (pintype "passive"))
    )
    (net (code "66") (name "Net-(PAIR_OPAMP_1B--IN)") (class "Default")
      (node (ref "PAIR_OPAMP_1") (pin "6") (pinfunction "-IN_6") (pintype "input"))
      (node (ref "RN3") (pin "1") (pinfunction "1_1") (pintype "passive"))
      (node (ref "RN3") (pin "2") (pinfunction "1_2") (pintype "passive"))
      (node (ref "RN3") (pin "5") (pinfunction "2_5") (pintype "passive"))
    )
    (net (code "67") (name "Net-(PAIR_OPAMP_2A-+IN)") (class "Default")
      (node (ref "PAIR_OPAMP_2") (pin "3") (pinfunction "+IN_3") (pintype "input"))
      (node (ref "RN5") (pin "5") (pinfunction "2_5") (pintype "passive"))
      (node (ref "RN5") (pin "7") (pinfunction "2_7") (pintype "passive"))
      (node (ref "RN5") (pin "8") (pinfunction "2_8") (pintype "passive"))
    )
    (net (code "68") (name "Net-(PAIR_OPAMP_2A--IN)") (class "Default")
      (node (ref "PAIR_OPAMP_2") (pin "2") (pinfunction "-IN_2") (pintype "input"))
      (node (ref "RN6") (pin "1") (pinfunction "1_1") (pintype "passive"))
      (node (ref "RN6") (pin "2") (pinfunction "1_2") (pintype "passive"))
      (node (ref "RN6") (pin "5") (pinfunction "2_5") (pintype "passive"))
    )
    (net (code "69") (name "Net-(PAIR_OPAMP_2B-+IN)") (class "Default")
      (node (ref "PAIR_OPAMP_2") (pin "5") (pinfunction "+IN_5") (pintype "input"))
      (node (ref "RN8") (pin "1") (pinfunction "1_1") (pintype "passive"))
      (node (ref "RN8") (pin "2") (pinfunction "1_2") (pintype "passive"))
      (node (ref "RN8") (pin "4") (pinfunction "1_4") (pintype "passive"))
    )
    (net (code "70") (name "Net-(PAIR_OPAMP_2B--IN)") (class "Default")
      (node (ref "PAIR_OPAMP_2") (pin "6") (pinfunction "-IN_6") (pintype "input"))
      (node (ref "RN7") (pin "1") (pinfunction "1_1") (pintype "passive"))
      (node (ref "RN7") (pin "2") (pinfunction "1_2") (pintype "passive"))
      (node (ref "RN7") (pin "5") (pinfunction "2_5") (pintype "passive"))
    )
    (net (code "71") (name "Net-(PAIR_OPAMP_3A-+IN)") (class "Default")
      (node (ref "PAIR_OPAMP_3") (pin "3") (pinfunction "+IN_3") (pintype "input"))
      (node (ref "RN9") (pin "5") (pinfunction "2_5") (pintype "passive"))
      (node (ref "RN9") (pin "7") (pinfunction "2_7") (pintype "passive"))
      (node (ref "RN9") (pin "8") (pinfunction "2_8") (pintype "passive"))
    )
    (net (code "72") (name "Net-(PAIR_OPAMP_3A--IN)") (class "Default")
      (node (ref "PAIR_OPAMP_3") (pin "2") (pinfunction "-IN_2") (pintype "input"))
      (node (ref "RN10") (pin "1") (pinfunction "1_1") (pintype "passive"))
      (node (ref "RN10") (pin "2") (pinfunction "1_2") (pintype "passive"))
      (node (ref "RN10") (pin "5") (pinfunction "2_5") (pintype "passive"))
    )
    (net (code "73") (name "Net-(PAIR_OPAMP_3B-+IN)") (class "Default")
      (node (ref "PAIR_OPAMP_3") (pin "5") (pinfunction "+IN_5") (pintype "input"))
      (node (ref "RN12") (pin "1") (pinfunction "1_1") (pintype "passive"))
      (node (ref "RN12") (pin "2") (pinfunction "1_2") (pintype "passive"))
      (node (ref "RN12") (pin "4") (pinfunction "1_4") (pintype "passive"))
    )
    (net (code "74") (name "Net-(PAIR_OPAMP_3B--IN)") (class "Default")
      (node (ref "PAIR_OPAMP_3") (pin "6") (pinfunction "-IN_6") (pintype "input"))
      (node (ref "RN11") (pin "1") (pinfunction "1_1") (pintype "passive"))
      (node (ref "RN11") (pin "2") (pinfunction "1_2") (pintype "passive"))
      (node (ref "RN11") (pin "5") (pinfunction "2_5") (pintype "passive"))
    )
    (net (code "75") (name "unconnected-(PAIR_GD_1-NC-Pad2)") (class "Default")
      (node (ref "PAIR_GD_1") (pin "2") (pinfunction "NC_2") (pintype "no_connect"))
    )
    (net (code "76") (name "unconnected-(PAIR_GD_1-NC-Pad4)") (class "Default")
      (node (ref "PAIR_GD_1") (pin "4") (pinfunction "NC_4") (pintype "no_connect"))
    )
    (net (code "77") (name "unconnected-(PAIR_GD_1-NC-Pad6)") (class "Default")
      (node (ref "PAIR_GD_1") (pin "6") (pinfunction "NC_6") (pintype "no_connect"))
    )
    (net (code "78") (name "unconnected-(PAIR_GD_1-NC-Pad11)") (class "Default")
      (node (ref "PAIR_GD_1") (pin "11") (pinfunction "NC_11") (pintype "no_connect"))
    )
    (net (code "79") (name "unconnected-(PAIR_GD_2-NC-Pad2)") (class "Default")
      (node (ref "PAIR_GD_2") (pin "2") (pinfunction "NC_2") (pintype "no_connect"))
    )
    (net (code "80") (name "unconnected-(PAIR_GD_2-NC-Pad4)") (class "Default")
      (node (ref "PAIR_GD_2") (pin "4") (pinfunction "NC_4") (pintype "no_connect"))
    )
    (net (code "81") (name "unconnected-(PAIR_GD_2-NC-Pad6)") (class "Default")
      (node (ref "PAIR_GD_2") (pin "6") (pinfunction "NC_6") (pintype "no_connect"))
    )
    (net (code "82") (name "unconnected-(PAIR_GD_2-NC-Pad11)") (class "Default")
      (node (ref "PAIR_GD_2") (pin "11") (pinfunction "NC_11") (pintype "no_connect"))
    )
    (net (code "83") (name "unconnected-(PAIR_GD_3-NC-Pad2)") (class "Default")
      (node (ref "PAIR_GD_3") (pin "2") (pinfunction "NC_2") (pintype "no_connect"))
    )
    (net (code "84") (name "unconnected-(PAIR_GD_3-NC-Pad4)") (class "Default")
      (node (ref "PAIR_GD_3") (pin "4") (pinfunction "NC_4") (pintype "no_connect"))
    )
    (net (code "85") (name "unconnected-(PAIR_GD_3-NC-Pad6)") (class "Default")
      (node (ref "PAIR_GD_3") (pin "6") (pinfunction "NC_6") (pintype "no_connect"))
    )
    (net (code "86") (name "unconnected-(PAIR_GD_3-NC-Pad11)") (class "Default")
      (node (ref "PAIR_GD_3") (pin "11") (pinfunction "NC_11") (pintype "no_connect"))
    )
  )
)
